# Smart_Stepper_Fin_-_Driver_Port.net
KiCad netlist of a schematic drawn in Altium Designer
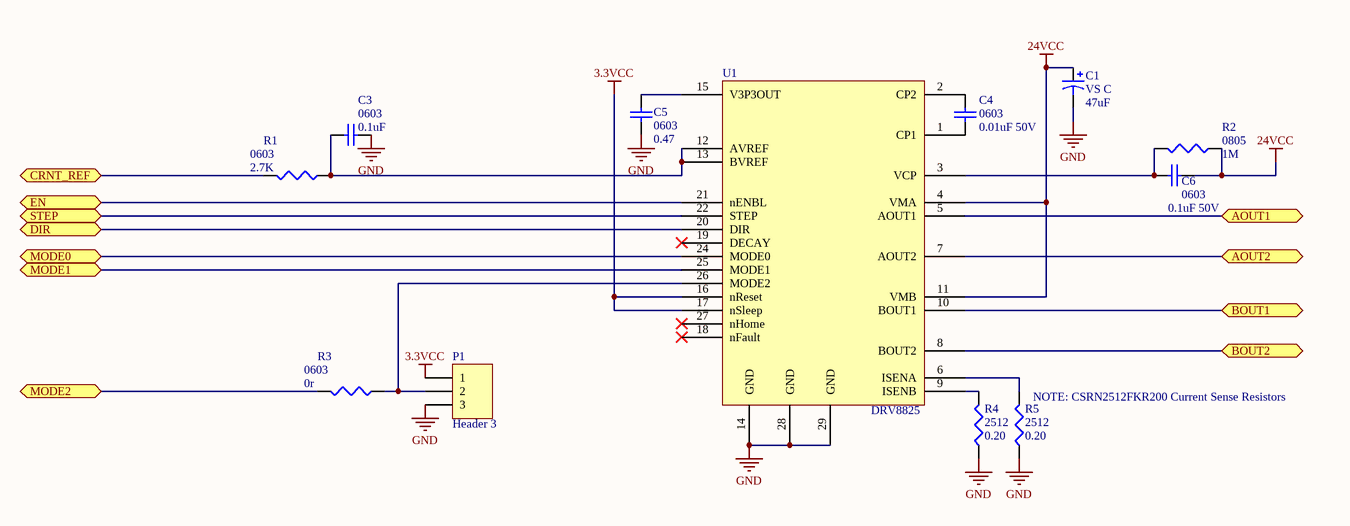
[diagram p0: Smart Stepper Fin - Driver & Port.SchDoc]

(export (version "E")
  (design (tool "Eeschema 10.0.6"))
  (components
    (comp (ref "C1")
      (value "VS C")
      (footprint "Panasonic VS C")
      (description "Polarized Capacitor (Radial)")
      (fields (field (name "ALTIUM_VALUE") "47uF") (field (name "PUBLISHER") "Altium Limited"))
      (libsource (lib "Miscellaneous Devices") (part "Cap Pol1"))
    )
    (comp (ref "C3")
      (value "0603")
      (footprint "1608[0603]")
      (description "Capacitor (Semiconductor SIM Model)")
      (fields (field (name "ALTIUM_VALUE") "0.1uF") (field (name "PUBLISHER") "Altium Limited"))
      (libsource (lib "Miscellaneous Devices") (part "Cap Semi"))
    )
    (comp (ref "C4")
      (value "0603")
      (footprint "1608[0603]")
      (description "Capacitor (Semiconductor SIM Model)")
      (fields (field (name "ALTIUM_VALUE") "0.01uF 50V") (field (name "PUBLISHER") "Altium Limited"))
      (libsource (lib "Miscellaneous Devices") (part "Cap Semi"))
    )
    (comp (ref "C5")
      (value "0603")
      (footprint "1608[0603]")
      (description "Capacitor (Semiconductor SIM Model)")
      (fields (field (name "ALTIUM_VALUE") "0.47") (field (name "PUBLISHER") "Altium Limited"))
      (libsource (lib "Miscellaneous Devices") (part "Cap Semi"))
    )
    (comp (ref "C6")
      (value "0603")
      (footprint "1608[0603]")
      (description "Capacitor (Semiconductor SIM Model)")
      (fields (field (name "ALTIUM_VALUE") "0.1uF 50V") (field (name "PUBLISHER") "Altium Limited"))
      (libsource (lib "Miscellaneous Devices") (part "Cap Semi"))
    )
    (comp (ref "P1")
      (value "Header 3")
      (footprint "HDR1X3")
      (description "Header, 3-Pin")
      (fields (field (name "PUBLISHER") "Altium Limited"))
      (libsource (lib "Miscellaneous Connectors") (part "Header 3"))
    )
    (comp (ref "R1")
      (value "0603")
      (footprint "J1-0603")
      (description "Resistor")
      (fields (field (name "ALTIUM_VALUE") "2.7K") (field (name "PUBLISHER") "Altium Limited"))
      (libsource (lib "Miscellaneous Devices") (part "Res3"))
    )
    (comp (ref "R2")
      (value "0805")
      (footprint "SM 0805 - gap trimmed")
      (description "Resistor")
      (fields (field (name "ALTIUM_VALUE") "1M") (field (name "PUBLISHER") "Altium Limited"))
      (libsource (lib "Miscellaneous Devices") (part "Res3"))
    )
    (comp (ref "R3")
      (value "0603")
      (footprint "J1-0603")
      (description "Resistor")
      (fields (field (name "ALTIUM_VALUE") "0r") (field (name "PUBLISHER") "Altium Limited"))
      (libsource (lib "Miscellaneous Devices") (part "Res3"))
    )
    (comp (ref "R4")
      (value "2512")
      (footprint "Resistor2512")
      (description "Resistor")
      (fields (field (name "ALTIUM_VALUE") "0.20") (field (name "PUBLISHER") "Altium Limited"))
      (libsource (lib "Miscellaneous Devices") (part "Res3"))
    )
    (comp (ref "R5")
      (value "2512")
      (footprint "Resistor2512")
      (description "Resistor")
      (fields (field (name "ALTIUM_VALUE") "0.20") (field (name "PUBLISHER") "Altium Limited"))
      (libsource (lib "Miscellaneous Devices") (part "Res3"))
    )
    (comp (ref "U1")
      (value "DRV8825")
      (footprint "DRV8825")
      (description "DRV8825 Ti Stepper Driver")
      (libsource (lib "ExtruderFinLib") (part "DRV8825"))
    )
  )
  (nets
    (net (code "1") (name "/AOUT1") (class "Default")
      (node (ref "U1") (pin "5") (pinfunction "AOUT1_5") (pintype "passive"))
    )
    (net (code "2") (name "/AOUT2") (class "Default")
      (node (ref "U1") (pin "7") (pinfunction "AOUT2_7") (pintype "passive"))
    )
    (net (code "3") (name "/BOUT1") (class "Default")
      (node (ref "U1") (pin "10") (pinfunction "BOUT1_10") (pintype "passive"))
    )
    (net (code "4") (name "/BOUT2") (class "Default")
      (node (ref "U1") (pin "8") (pinfunction "BOUT2_8") (pintype "passive"))
    )
    (net (code "5") (name "/CRNT_REF") (class "Default")
      (node (ref "R1") (pin "2") (pinfunction "2_2") (pintype "passive"))
    )
    (net (code "6") (name "/DIR") (class "Default")
      (node (ref "U1") (pin "20") (pinfunction "DIR_20") (pintype "passive"))
    )
    (net (code "7") (name "/EN") (class "Default")
      (node (ref "U1") (pin "21") (pinfunction "nENBL_21") (pintype "passive"))
    )
    (net (code "8") (name "/MODE0") (class "Default")
      (node (ref "U1") (pin "24") (pinfunction "MODE0_24") (pintype "passive"))
    )
    (net (code "9") (name "/MODE1") (class "Default")
      (node (ref "U1") (pin "25") (pinfunction "MODE1_25") (pintype "passive"))
    )
    (net (code "10") (name "/MODE2") (class "Default")
      (node (ref "R3") (pin "2") (pinfunction "2_2") (pintype "passive"))
    )
    (net (code "11") (name "/STEP") (class "Default")
      (node (ref "U1") (pin "22") (pinfunction "STEP_22") (pintype "passive"))
    )
    (net (code "12") (name "3.3VCC") (class "Default")
      (node (ref "P1") (pin "1") (pinfunction "1_1") (pintype "passive"))
      (node (ref "U1") (pin "16") (pinfunction "nReset_16") (pintype "passive"))
      (node (ref "U1") (pin "17") (pinfunction "nSleep_17") (pintype "passive"))
    )
    (net (code "13") (name "24VCC") (class "Default")
      (node (ref "C1") (pin "1") (pinfunction "1_1") (pintype "passive"))
      (node (ref "C6") (pin "1") (pinfunction "1_1") (pintype "passive"))
      (node (ref "R2") (pin "1") (pinfunction "1_1") (pintype "passive"))
      (node (ref "U1") (pin "11") (pinfunction "VMB_11") (pintype "passive"))
      (node (ref "U1") (pin "4") (pinfunction "VMA_4") (pintype "passive"))
    )
    (net (code "14") (name "GND") (class "Default")
      (node (ref "C1") (pin "2") (pinfunction "2_2") (pintype "passive"))
      (node (ref "C3") (pin "1") (pinfunction "1_1") (pintype "passive"))
      (node (ref "C5") (pin "1") (pinfunction "1_1") (pintype "passive"))
      (node (ref "P1") (pin "3") (pinfunction "3_3") (pintype "passive"))
      (node (ref "R4") (pin "1") (pinfunction "1_1") (pintype "passive"))
      (node (ref "R5") (pin "1") (pinfunction "1_1") (pintype "passive"))
      (node (ref "U1") (pin "14") (pinfunction "GND_14") (pintype "passive"))
      (node (ref "U1") (pin "28") (pinfunction "GND_28") (pintype "passive"))
      (node (ref "U1") (pin "29") (pinfunction "GND_29") (pintype "passive"))
    )
    (net (code "15") (name "Net-(U1-AVREF)") (class "Default")
      (node (ref "C3") (pin "2") (pinfunction "2_2") (pintype "passive"))
      (node (ref "R1") (pin "1") (pinfunction "1_1") (pintype "passive"))
      (node (ref "U1") (pin "12") (pinfunction "AVREF_12") (pintype "passive"))
      (node (ref "U1") (pin "13") (pinfunction "BVREF_13") (pintype "passive"))
    )
    (net (code "16") (name "Net-(U1-CP1)") (class "Default")
      (node (ref "C4") (pin "1") (pinfunction "1_1") (pintype "passive"))
      (node (ref "U1") (pin "1") (pinfunction "CP1_1") (pintype "passive"))
    )
    (net (code "17") (name "Net-(U1-CP2)") (class "Default")
      (node (ref "C4") (pin "2") (pinfunction "2_2") (pintype "passive"))
      (node (ref "U1") (pin "2") (pinfunction "CP2_2") (pintype "passive"))
    )
    (net (code "18") (name "Net-(U1-ISENA)") (class "Default")
      (node (ref "R5") (pin "2") (pinfunction "2_2") (pintype "passive"))
      (node (ref "U1") (pin "6") (pinfunction "ISENA_6") (pintype "passive"))
    )
    (net (code "19") (name "Net-(U1-ISENB)") (class "Default")
      (node (ref "R4") (pin "2") (pinfunction "2_2") (pintype "passive"))
      (node (ref "U1") (pin "9") (pinfunction "ISENB_9") (pintype "passive"))
    )
    (net (code "20") (name "Net-(U1-MODE2)") (class "Default")
      (node (ref "P1") (pin "2") (pinfunction "2_2") (pintype "passive"))
      (node (ref "R3") (pin "1") (pinfunction "1_1") (pintype "passive"))
      (node (ref "U1") (pin "26") (pinfunction "MODE2_26") (pintype "passive"))
    )
    (net (code "21") (name "Net-(U1-V3P3OUT)") (class "Default")
      (node (ref "C5") (pin "2") (pinfunction "2_2") (pintype "passive"))
      (node (ref "U1") (pin "15") (pinfunction "V3P3OUT_15") (pintype "passive"))
    )
    (net (code "22") (name "Net-(U1-VCP)") (class "Default")
      (node (ref "C6") (pin "2") (pinfunction "2_2") (pintype "passive"))
      (node (ref "R2") (pin "2") (pinfunction "2_2") (pintype "passive"))
      (node (ref "U1") (pin "3") (pinfunction "VCP_3") (pintype "passive"))
    )
    (net (code "23") (name "unconnected-(U1-DECAY-Pad19)") (class "Default")
      (node (ref "U1") (pin "19") (pinfunction "DECAY_19") (pintype "passive+no_connect"))
    )
    (net (code "24") (name "unconnected-(U1-NC-Pad23)") (class "Default")
      (node (ref "U1") (pin "23") (pinfunction "NC_23") (pintype "passive"))
    )
    (net (code "25") (name "unconnected-(U1-nFault-Pad18)") (class "Default")
      (node (ref "U1") (pin "18") (pinfunction "nFault_18") (pintype "passive+no_connect"))
    )
    (net (code "26") (name "unconnected-(U1-nHome-Pad27)") (class "Default")
      (node (ref "U1") (pin "27") (pinfunction "nHome_27") (pintype "passive+no_connect"))
    )
  )
)
